# Steering_Wheel_Carrier_Board_Mezzanine.net
KiCad netlist of a schematic drawn in Altium Designer
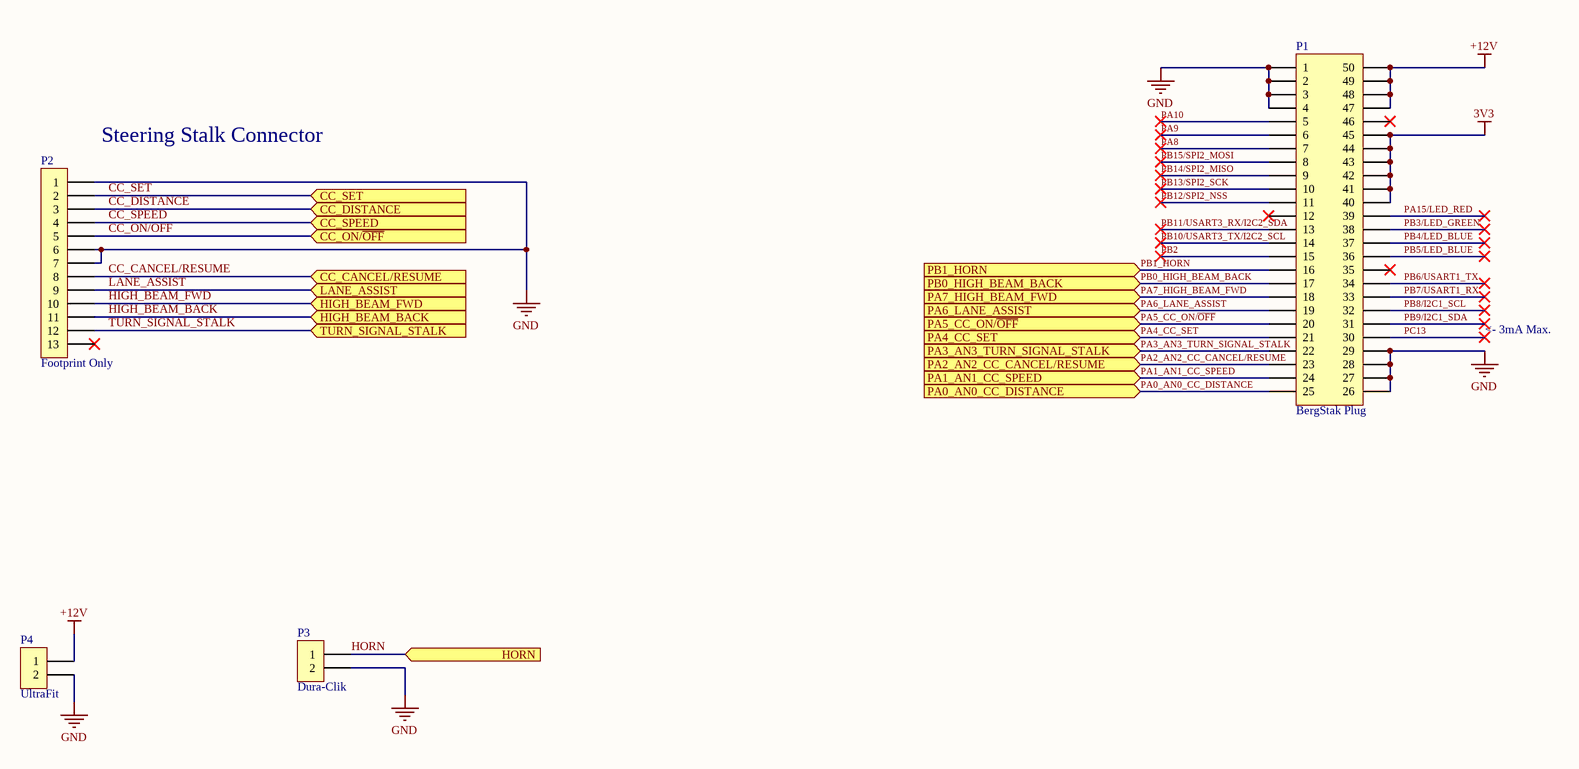
[diagram p0: Steering Wheel Carrier Board Mezzanine.SchDoc]

(export (version "E")
  (design (tool "Eeschema 10.0.6"))
  (components
    (comp (ref "P1")
      (value "CONN 50POS Bergstak Plug 0.02\"")
      (footprint "CONN, Bergstak 50 Pos Plug")
      (description "50 Position Connector Plug, Outer Shroud Contacts Surface Mount Gold")
      (fields (field (name "SERIES") "BergStak Plug"))
      (libsource (lib "Schematic Diagrams") (part "CONN 50POS Bergstak Plug 0.02{dblquote}"))
    )
    (comp (ref "P2")
      (value "Footprint Only")
      (footprint "CONN 13POS CARD EDGE")
      (libsource (lib "Schematic Diagrams") (part "CONN 13POS 0.1{dblquote} CARD EDGE"))
    )
    (comp (ref "P3")
      (value "Dura-Clik")
      (footprint "CONN, 2POS Dura-Click Vertical")
      (description "2 Positions Header, Shrouded Connector 0.079\" (2.00mm) Surface Mount, Vertical Tin")
      (fields
        (field (name "MANUFACTURER") "Molex, LLC")
        (field (name "MANUFACTURER PART NUMBER") "5600200220")
      )
      (libsource (lib "Schematic Diagrams") (part "CONN 2POS DURA-CLIK 0.079{dblquote} VERT"))
    )
    (comp (ref "P4")
      (value "CONN 2POS ULTRA-FIT 0.138\"")
      (footprint "CONN, 2POS ULTRA-FIT")
      (description "2 Positions Header, Shrouded Connector 0.138\" (3.50mm) Through Hole Gold")
      (fields (field (name "VOLTAGE") "400V") (field (name "SERIES") "UltraFit"))
      (libsource (lib "Schematic Diagrams") (part "CONN 2POS ULTRA-FIT 0.138{dblquote}"))
    )
  )
  (nets
    (net (code "1") (name "+12V") (class "Default")
      (node (ref "P1") (pin "47") (pinfunction "47_47") (pintype "passive"))
      (node (ref "P1") (pin "48") (pinfunction "48_48") (pintype "passive"))
      (node (ref "P1") (pin "49") (pinfunction "49_49") (pintype "passive"))
      (node (ref "P1") (pin "50") (pinfunction "50_50") (pintype "passive"))
      (node (ref "P4") (pin "1") (pinfunction "1_1") (pintype "passive"))
    )
    (net (code "2") (name "/CC_CANCEL{slash}RESUME") (class "Default")
      (node (ref "P2") (pin "8") (pinfunction "8_8") (pintype "passive"))
    )
    (net (code "3") (name "/CC_DISTANCE") (class "Default")
      (node (ref "P2") (pin "3") (pinfunction "3_3") (pintype "passive"))
    )
    (net (code "4") (name "/CC_ON{slash}~{OFF}") (class "Default")
      (node (ref "P2") (pin "5") (pinfunction "5_5") (pintype "passive"))
    )
    (net (code "5") (name "/CC_SET") (class "Default")
      (node (ref "P2") (pin "2") (pinfunction "2_2") (pintype "passive"))
    )
    (net (code "6") (name "/CC_SPEED") (class "Default")
      (node (ref "P2") (pin "4") (pinfunction "4_4") (pintype "passive"))
    )
    (net (code "7") (name "/HIGH_BEAM_BACK") (class "Default")
      (node (ref "P2") (pin "11") (pinfunction "11_11") (pintype "passive"))
    )
    (net (code "8") (name "/HIGH_BEAM_FWD") (class "Default")
      (node (ref "P2") (pin "10") (pinfunction "10_10") (pintype "passive"))
    )
    (net (code "9") (name "/HORN") (class "Default")
      (node (ref "P3") (pin "1") (pinfunction "1_1") (pintype "passive"))
    )
    (net (code "10") (name "/LANE_ASSIST") (class "Default")
      (node (ref "P2") (pin "9") (pinfunction "9_9") (pintype "passive"))
    )
    (net (code "11") (name "/PA0_AN0_CC_DISTANCE") (class "Default")
      (node (ref "P1") (pin "25") (pinfunction "25_25") (pintype "passive"))
    )
    (net (code "12") (name "/PA1_AN1_CC_SPEED") (class "Default")
      (node (ref "P1") (pin "24") (pinfunction "24_24") (pintype "passive"))
    )
    (net (code "13") (name "/PA2_AN2_CC_CANCEL{slash}RESUME") (class "Default")
      (node (ref "P1") (pin "23") (pinfunction "23_23") (pintype "passive"))
    )
    (net (code "14") (name "/PA3_AN3_TURN_SIGNAL_STALK") (class "Default")
      (node (ref "P1") (pin "22") (pinfunction "22_22") (pintype "passive"))
    )
    (net (code "15") (name "/PA4_CC_SET") (class "Default")
      (node (ref "P1") (pin "21") (pinfunction "21_21") (pintype "passive"))
    )
    (net (code "16") (name "/PA5_CC_ON{slash}~{OFF}") (class "Default")
      (node (ref "P1") (pin "20") (pinfunction "20_20") (pintype "passive"))
    )
    (net (code "17") (name "/PA6_LANE_ASSIST") (class "Default")
      (node (ref "P1") (pin "19") (pinfunction "19_19") (pintype "passive"))
    )
    (net (code "18") (name "/PA7_HIGH_BEAM_FWD") (class "Default")
      (node (ref "P1") (pin "18") (pinfunction "18_18") (pintype "passive"))
    )
    (net (code "19") (name "/PA8") (class "Default")
      (node (ref "P1") (pin "7") (pinfunction "7_7") (pintype "passive+no_connect"))
    )
    (net (code "20") (name "/PA9") (class "Default")
      (node (ref "P1") (pin "6") (pinfunction "6_6") (pintype "passive+no_connect"))
    )
    (net (code "21") (name "/PA10") (class "Default")
      (node (ref "P1") (pin "5") (pinfunction "5_5") (pintype "passive+no_connect"))
    )
    (net (code "22") (name "/PA15{slash}LED_RED") (class "Default")
      (node (ref "P1") (pin "39") (pinfunction "39_39") (pintype "passive+no_connect"))
    )
    (net (code "23") (name "/PB0_HIGH_BEAM_BACK") (class "Default")
      (node (ref "P1") (pin "17") (pinfunction "17_17") (pintype "passive"))
    )
    (net (code "24") (name "/PB1_HORN") (class "Default")
      (node (ref "P1") (pin "16") (pinfunction "16_16") (pintype "passive"))
    )
    (net (code "25") (name "/PB2") (class "Default")
      (node (ref "P1") (pin "15") (pinfunction "15_15") (pintype "passive+no_connect"))
    )
    (net (code "26") (name "/PB3{slash}LED_GREEN") (class "Default")
      (node (ref "P1") (pin "38") (pinfunction "38_38") (pintype "passive+no_connect"))
    )
    (net (code "27") (name "/PB4{slash}LED_BLUE") (class "Default")
      (node (ref "P1") (pin "37") (pinfunction "37_37") (pintype "passive+no_connect"))
    )
    (net (code "28") (name "/PB5{slash}LED_BLUE") (class "Default")
      (node (ref "P1") (pin "36") (pinfunction "36_36") (pintype "passive+no_connect"))
    )
    (net (code "29") (name "/PB6{slash}USART1_TX") (class "Default")
      (node (ref "P1") (pin "34") (pinfunction "34_34") (pintype "passive+no_connect"))
    )
    (net (code "30") (name "/PB7{slash}USART1_RX") (class "Default")
      (node (ref "P1") (pin "33") (pinfunction "33_33") (pintype "passive+no_connect"))
    )
    (net (code "31") (name "/PB8{slash}I2C1_SCL") (class "Default")
      (node (ref "P1") (pin "32") (pinfunction "32_32") (pintype "passive+no_connect"))
    )
    (net (code "32") (name "/PB9{slash}I2C1_SDA") (class "Default")
      (node (ref "P1") (pin "31") (pinfunction "31_31") (pintype "passive+no_connect"))
    )
    (net (code "33") (name "/PB10{slash}USART3_TX{slash}I2C2_SCL") (class "Default")
      (node (ref "P1") (pin "14") (pinfunction "14_14") (pintype "passive+no_connect"))
    )
    (net (code "34") (name "/PB11{slash}USART3_RX{slash}I2C2_SDA") (class "Default")
      (node (ref "P1") (pin "13") (pinfunction "13_13") (pintype "passive+no_connect"))
    )
    (net (code "35") (name "/PB12{slash}SPI2_NSS") (class "Default")
      (node (ref "P1") (pin "11") (pinfunction "11_11") (pintype "passive+no_connect"))
    )
    (net (code "36") (name "/PB13{slash}SPI2_SCK") (class "Default")
      (node (ref "P1") (pin "10") (pinfunction "10_10") (pintype "passive+no_connect"))
    )
    (net (code "37") (name "/PB14{slash}SPI2_MISO") (class "Default")
      (node (ref "P1") (pin "9") (pinfunction "9_9") (pintype "passive+no_connect"))
    )
    (net (code "38") (name "/PB15{slash}SPI2_MOSI") (class "Default")
      (node (ref "P1") (pin "8") (pinfunction "8_8") (pintype "passive+no_connect"))
    )
    (net (code "39") (name "/PC13") (class "Default")
      (node (ref "P1") (pin "30") (pinfunction "30_30") (pintype "passive+no_connect"))
    )
    (net (code "40") (name "/TURN_SIGNAL_STALK") (class "Default")
      (node (ref "P2") (pin "12") (pinfunction "12_12") (pintype "passive"))
    )
    (net (code "41") (name "3V3") (class "Default")
      (node (ref "P1") (pin "40") (pinfunction "40_40") (pintype "passive"))
      (node (ref "P1") (pin "41") (pinfunction "41_41") (pintype "passive"))
      (node (ref "P1") (pin "42") (pinfunction "42_42") (pintype "passive"))
      (node (ref "P1") (pin "43") (pinfunction "43_43") (pintype "passive"))
      (node (ref "P1") (pin "44") (pinfunction "44_44") (pintype "passive"))
      (node (ref "P1") (pin "45") (pinfunction "45_45") (pintype "passive"))
    )
    (net (code "42") (name "GND") (class "Default")
      (node (ref "P1") (pin "1") (pinfunction "1_1") (pintype "passive"))
      (node (ref "P1") (pin "2") (pinfunction "2_2") (pintype "passive"))
      (node (ref "P1") (pin "26") (pinfunction "26_26") (pintype "passive"))
      (node (ref "P1") (pin "27") (pinfunction "27_27") (pintype "passive"))
      (node (ref "P1") (pin "28") (pinfunction "28_28") (pintype "passive"))
      (node (ref "P1") (pin "29") (pinfunction "29_29") (pintype "passive"))
      (node (ref "P1") (pin "3") (pinfunction "3_3") (pintype "passive"))
      (node (ref "P1") (pin "4") (pinfunction "4_4") (pintype "passive"))
      (node (ref "P2") (pin "1") (pinfunction "1_1") (pintype "passive"))
      (node (ref "P2") (pin "6") (pinfunction "6_6") (pintype "passive"))
      (node (ref "P2") (pin "7") (pinfunction "7_7") (pintype "passive"))
      (node (ref "P3") (pin "2") (pinfunction "2_2") (pintype "passive"))
      (node (ref "P4") (pin "2") (pinfunction "2_2") (pintype "passive"))
    )
    (net (code "43") (name "unconnected-(P1-Pad12)") (class "Default")
      (node (ref "P1") (pin "12") (pinfunction "12_12") (pintype "passive+no_connect"))
    )
    (net (code "44") (name "unconnected-(P1-Pad35)") (class "Default")
      (node (ref "P1") (pin "35") (pinfunction "35_35") (pintype "passive+no_connect"))
    )
    (net (code "45") (name "unconnected-(P1-Pad46)") (class "Default")
      (node (ref "P1") (pin "46") (pinfunction "46_46") (pintype "passive+no_connect"))
    )
    (net (code "46") (name "unconnected-(P2-Pad13)") (class "Default")
      (node (ref "P2") (pin "13") (pinfunction "13_13") (pintype "passive+no_connect"))
    )
  )
)
